# Teensylu2-1_0.net
KiCad netlist of a schematic drawn in EAGLE
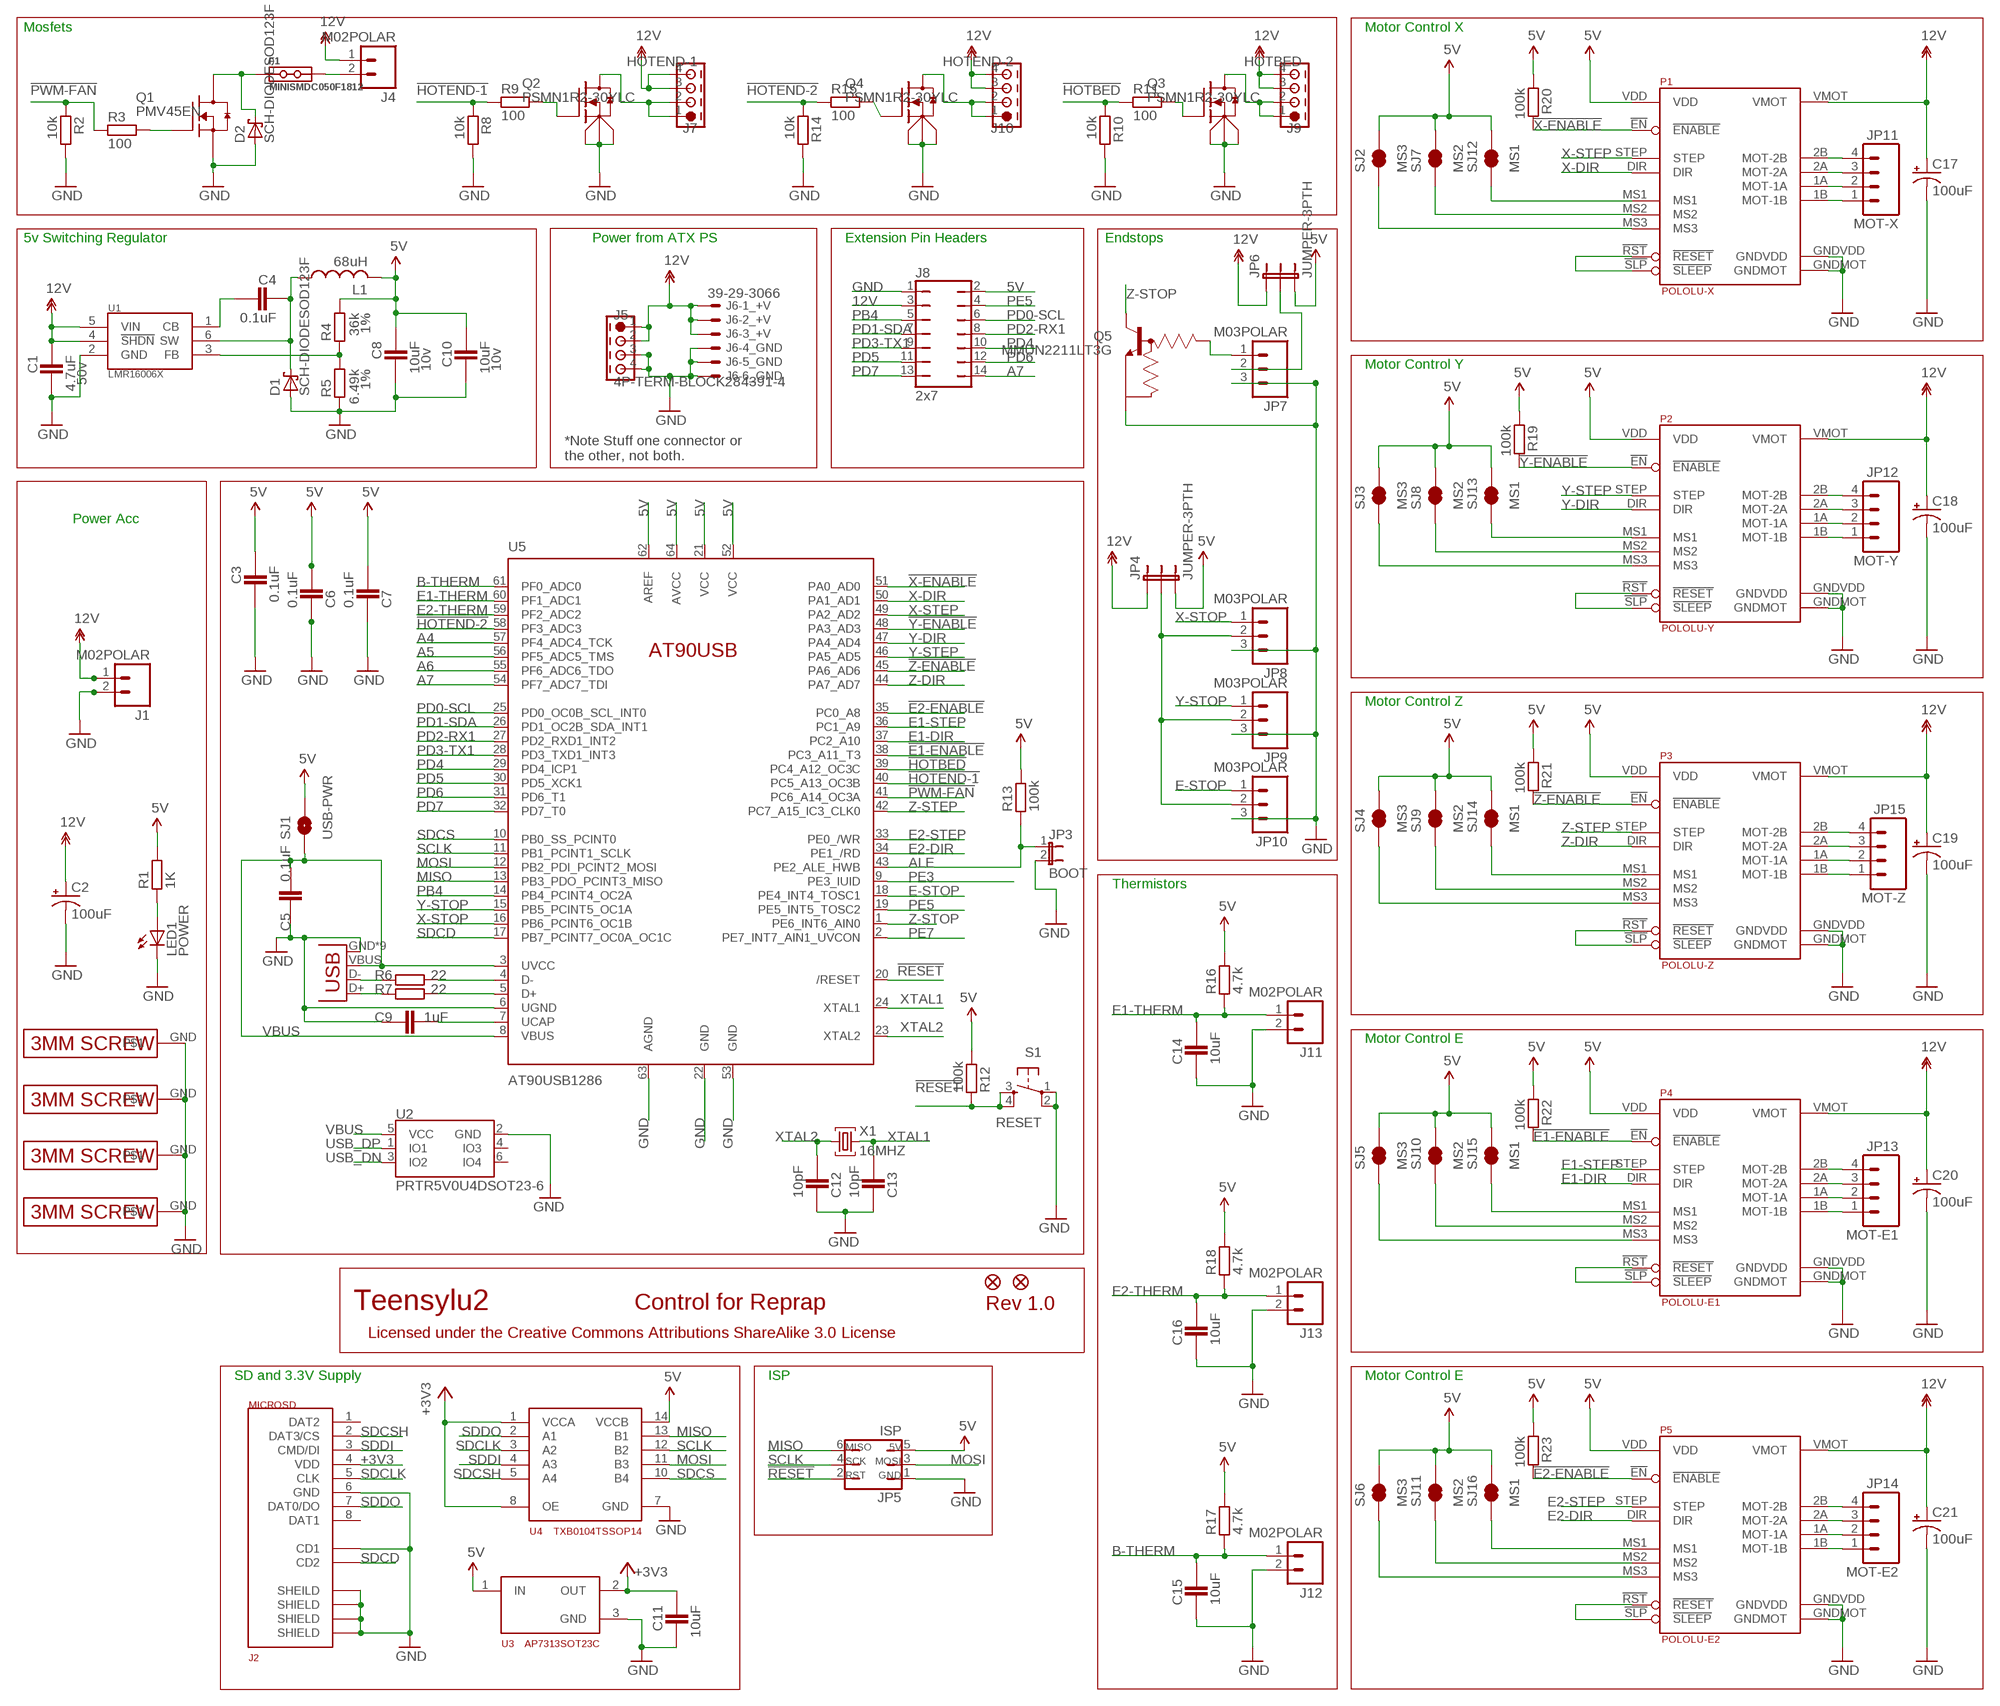
[diagram p0: schematic, sheet 1]

(export (version "E")
  (design (tool "Eeschema 10.0.6"))
  (components
    (comp (ref "C1")
      (value "4.7uF")
      (footprint "eagle-import:CAPC3215X168N")
      (fields
        (field (name "MANUFACTURER") "Yaiyo Yuden")
        (field (name "MANUFACTURER_PART_NUMBER") "UMK316AB7475KL-T")
        (field (name "TOLERANCE") "10%")
        (field (name "VDC") "50v")
      )
      (libsource (lib "eagle-import") (part "CAPACITOR_1206"))
    )
    (comp (ref "C2")
      (value "100uF")
      (footprint "eagle-import:PANASONIC_D")
      (fields
        (field (name "MANUFACTURER") "Panasonic")
        (field (name "MANUFACTURER_PART_NUMBER") "EEE-FTH101XAP")
        (field (name "TOLERANCE") "20%")
      )
      (libsource (lib "eagle-import") (part "CPOL-USD"))
    )
    (comp (ref "C3")
      (value "0.1uF")
      (footprint "eagle-import:CAPC1608X92N")
      (fields
        (field (name "MANUFACTURER") "Murata")
        (field (name "MANUFACTURER_PART_NUMBER") "GRM188R71C104KA01D")
        (field (name "TOLERANCE") "10%")
      )
      (libsource (lib "eagle-import") (part "CAPACITOR_0603"))
    )
    (comp (ref "C4")
      (value "0.1uF")
      (footprint "eagle-import:CAPC1608X92N")
      (fields
        (field (name "MANUFACTURER") "Samsung")
        (field (name "MANUFACTURER_PART_NUMBER") "CL10B104KB8NNNC")
        (field (name "TOLERANCE") "10%")
      )
      (libsource (lib "eagle-import") (part "CAPACITOR_0603"))
    )
    (comp (ref "C5")
      (value "0.1uF")
      (footprint "eagle-import:CAPC1608X92N")
      (fields
        (field (name "MANUFACTURER") "Murata")
        (field (name "MANUFACTURER_PART_NUMBER") "GRM188R71C104KA01D")
        (field (name "TOLERANCE") "10%")
      )
      (libsource (lib "eagle-import") (part "CAPACITOR_0603"))
    )
    (comp (ref "C6")
      (value "0.1uF")
      (footprint "eagle-import:CAPC1608X92N")
      (fields
        (field (name "MANUFACTURER") "Murata")
        (field (name "MANUFACTURER_PART_NUMBER") "GRM188R71C104KA01D")
        (field (name "TOLERANCE") "10%")
      )
      (libsource (lib "eagle-import") (part "CAPACITOR_0603"))
    )
    (comp (ref "C7")
      (value "0.1uF")
      (footprint "eagle-import:CAPC1608X92N")
      (fields
        (field (name "MANUFACTURER") "Murata")
        (field (name "MANUFACTURER_PART_NUMBER") "GRM188R71C104KA01D")
        (field (name "TOLERANCE") "10%")
      )
      (libsource (lib "eagle-import") (part "CAPACITOR_0603"))
    )
    (comp (ref "C8")
      (value "10uF")
      (footprint "eagle-import:CAPC2012X145AN")
      (fields
        (field (name "MANUFACTURER") "Murata")
        (field (name "MANUFACTURER_PART_NUMBER") "GRM21BR71A106KE51L")
        (field (name "TOLERANCE") "10%")
        (field (name "VDC") "10v")
      )
      (libsource (lib "eagle-import") (part "CAPACITOR_0805"))
    )
    (comp (ref "C9")
      (value "1uF")
      (footprint "eagle-import:CAPC1608X92N")
      (fields
        (field (name "MANUFACTURER") "Samsung")
        (field (name "MANUFACTURER_PART_NUMBER") "CL10A105MO8NNNC")
        (field (name "TOLERANCE") "20%")
      )
      (libsource (lib "eagle-import") (part "CAPACITOR_0603"))
    )
    (comp (ref "C10")
      (value "10uF")
      (footprint "eagle-import:CAPC2012X145AN")
      (fields
        (field (name "MANUFACTURER") "Murata")
        (field (name "MANUFACTURER_PART_NUMBER") "GRM21BR71A106KE51L")
        (field (name "TOLERANCE") "10%")
        (field (name "VDC") "10v")
      )
      (libsource (lib "eagle-import") (part "CAPACITOR_0805"))
    )
    (comp (ref "C11")
      (value "10uF")
      (footprint "eagle-import:CAPC1608X92N")
      (fields
        (field (name "MANUFACTURER") "Murata")
        (field (name "MANUFACTURER_PART_NUMBER") "GRM188R61C106MA73D")
        (field (name "TOLERANCE") "20%")
      )
      (libsource (lib "eagle-import") (part "CAPACITOR_0603"))
    )
    (comp (ref "C12")
      (value "10pF")
      (footprint "eagle-import:CAPC1608X92N")
      (fields
        (field (name "MANUFACTURER") "Samsung")
        (field (name "MANUFACTURER_PART_NUMBER") "CL10C100JB8NCNC")
        (field (name "TOLERANCE") "5%")
      )
      (libsource (lib "eagle-import") (part "CAPACITOR_0603"))
    )
    (comp (ref "C13")
      (value "10pF")
      (footprint "eagle-import:CAPC1608X92N")
      (fields
        (field (name "MANUFACTURER") "Samsung")
        (field (name "MANUFACTURER_PART_NUMBER") "CL10C100JB8NCNC")
        (field (name "TOLERANCE") "5%")
      )
      (libsource (lib "eagle-import") (part "CAPACITOR_0603"))
    )
    (comp (ref "C14")
      (value "10uF")
      (footprint "eagle-import:CAPC1608X92N")
      (fields
        (field (name "MANUFACTURER") "Murata")
        (field (name "MANUFACTURER_PART_NUMBER") "GRM188R61C106MA73D")
        (field (name "TOLERANCE") "20%")
      )
      (libsource (lib "eagle-import") (part "CAPACITOR_0603"))
    )
    (comp (ref "C15")
      (value "10uF")
      (footprint "eagle-import:CAPC1608X92N")
      (fields
        (field (name "MANUFACTURER") "Murata")
        (field (name "MANUFACTURER_PART_NUMBER") "GRM188R61C106MA73D")
        (field (name "TOLERANCE") "20%")
      )
      (libsource (lib "eagle-import") (part "CAPACITOR_0603"))
    )
    (comp (ref "C16")
      (value "10uF")
      (footprint "eagle-import:CAPC1608X92N")
      (fields
        (field (name "MANUFACTURER") "Murata")
        (field (name "MANUFACTURER_PART_NUMBER") "GRM188R61C106MA73D")
        (field (name "TOLERANCE") "20%")
      )
      (libsource (lib "eagle-import") (part "CAPACITOR_0603"))
    )
    (comp (ref "C17")
      (value "100uF")
      (footprint "eagle-import:PANASONIC_D")
      (fields
        (field (name "MANUFACTURER") "Panasonic")
        (field (name "MANUFACTURER_PART_NUMBER") "EEE-FTH101XAP")
        (field (name "TOLERANCE") "20%")
      )
      (libsource (lib "eagle-import") (part "CPOL-USD"))
    )
    (comp (ref "C18")
      (value "100uF")
      (footprint "eagle-import:PANASONIC_D")
      (fields
        (field (name "MANUFACTURER") "Panasonic")
        (field (name "MANUFACTURER_PART_NUMBER") "EEE-FTH101XAP")
        (field (name "TOLERANCE") "20%")
      )
      (libsource (lib "eagle-import") (part "CPOL-USD"))
    )
    (comp (ref "C19")
      (value "100uF")
      (footprint "eagle-import:PANASONIC_D")
      (fields
        (field (name "MANUFACTURER") "Panasonic")
        (field (name "MANUFACTURER_PART_NUMBER") "EEE-FTH101XAP")
        (field (name "TOLERANCE") "20%")
      )
      (libsource (lib "eagle-import") (part "CPOL-USD"))
    )
    (comp (ref "C20")
      (value "100uF")
      (footprint "eagle-import:PANASONIC_D")
      (fields
        (field (name "MANUFACTURER") "Panasonic")
        (field (name "MANUFACTURER_PART_NUMBER") "EEE-FTH101XAP")
        (field (name "TOLERANCE") "20%")
      )
      (libsource (lib "eagle-import") (part "CPOL-USD"))
    )
    (comp (ref "C21")
      (value "100uF")
      (footprint "eagle-import:PANASONIC_D")
      (fields
        (field (name "MANUFACTURER") "Panasonic")
        (field (name "MANUFACTURER_PART_NUMBER") "EEE-FTH101XAP")
        (field (name "TOLERANCE") "20%")
      )
      (libsource (lib "eagle-import") (part "CPOL-USD"))
    )
    (comp (ref "D1")
      (value "SCH-DIODESOD123F")
      (footprint "eagle-import:SOD123F")
      (fields
        (field (name "MANUFACTURER") "NXP Semiconductors")
        (field (name "MANUFACTURER_PART_NUMBER") "PMEG4010CEH,115")
        (field (name "CURRENT") "1A")
        (field (name "MANUFACTURER_1") "NXP Semiconductors")
        (field (name "MANUFACTURER_PART_NUMBER_1") "PMEG4010CEH,115")
        (field (name "REVERSE_VOLTAGE") "40V")
      )
      (libsource (lib "eagle-import") (part "SCH-DIODESOD123F"))
    )
    (comp (ref "D2")
      (value "SCH-DIODESOD123F")
      (footprint "eagle-import:SOD123F")
      (fields
        (field (name "MANUFACTURER") "NXP Semiconductors")
        (field (name "MANUFACTURER_PART_NUMBER") "PMEG4010CEH,115")
        (field (name "CURRENT") "1A")
        (field (name "MANUFACTURER_1") "NXP Semiconductors")
      )
      (libsource (lib "eagle-import") (part "SCH-DIODESOD123F"))
    )
    (comp (ref "F1")
      (value "MINISMDC050F1812")
      (footprint "eagle-import:MINISMDC")
      (fields
        (field (name "MANUFACTURER") "TE Connectivity")
        (field (name "MANUFACTURER_PART_NUMBER") "MINISMDC050F-2")
      )
      (libsource (lib "eagle-import") (part "MINISMDC050F1812"))
    )
    (comp (ref "J1")
      (value "M02POLAR")
      (footprint "eagle-import:MOLEX-1X2")
      (description "CONN HEADER 2POS .100 VERT TIN")
      (fields (field (name "MANUFACTURER") "Molex") (field (name "MANUFACTURER_PART_NUMBER") "0022272021"))
      (libsource (lib "eagle-import") (part "M02POLAR"))
    )
    (comp (ref "J2")
      (value "MICROSD")
      (footprint "eagle-import:AMPHENOL-MICROSD")
      (description "CONN MICRO SD CARD PUSH-PULL R/A")
      (fields
        (field (name "MANUFACTURER") "Amphenol")
        (field (name "MANUFACTURER_PART_NUMBER") "114-00841-68")
      )
      (libsource (lib "eagle-import") (part "MICROSD"))
    )
    (comp (ref "J3")
      (value "USB-MICRO-PTH")
      (footprint "eagle-import:USB-MICROB-PTH")
      (fields (field (name "MANUFACTURER") "FCI") (field (name "MANUFACTURER_PART_NUMBER") "10118194-0001LF"))
      (libsource (lib "eagle-import") (part "USB-MICRO-PTH"))
    )
    (comp (ref "J4")
      (value "M02POLAR")
      (footprint "eagle-import:MOLEX-1X2")
      (description "CONN HEADER 2POS .100 VERT TIN")
      (fields (field (name "MANUFACTURER") "Molex") (field (name "MANUFACTURER_PART_NUMBER") "0022272021"))
      (libsource (lib "eagle-import") (part "M02POLAR"))
    )
    (comp (ref "J5")
      (value "4P-TERM-BLOCK284391-4")
      (footprint "eagle-import:284391-4")
      (fields
        (field (name "MANUFACTURER") "TE Connectivity")
        (field (name "MANUFACTURER_PART_NUMBER") "284391-4")
      )
      (libsource (lib "eagle-import") (part "4P-TERM-BLOCK284391-4"))
    )
    (comp (ref "J6")
      (value "39-29-3066")
      (footprint "eagle-import:39-29-3066")
      (fields (field (name "MANUFACTURER") "Molex") (field (name "MANUFACTURER_PART_NUMBER") "0039293066"))
      (libsource (lib "eagle-import") (part "39-29-3066"))
    )
    (comp (ref "J7")
      (value "HOTEND-1")
      (footprint "eagle-import:282834-4")
      (fields
        (field (name "MANUFACTURER") "TE Connectivity")
        (field (name "MANUFACTURER_PART_NUMBER") "282834-4")
      )
      (libsource (lib "eagle-import") (part "4P-TERM-BLOCK282834-4"))
    )
    (comp (ref "J8")
      (value "2x7")
      (footprint "eagle-import:JP7Q")
      (description "DIL VERTICAL PC TAIL PIN HEADER")
      (fields (field (name "MANUFACTURER") "Harwin") (field (name "MANUFACTURER_PART_NUMBER") "M20-9980746"))
      (libsource (lib "eagle-import") (part "JP7Q"))
    )
    (comp (ref "J9")
      (value "HOTBED")
      (footprint "eagle-import:284391-4")
      (fields
        (field (name "MANUFACTURER") "TE Connectivity")
        (field (name "MANUFACTURER_PART_NUMBER") "284391-4")
      )
      (libsource (lib "eagle-import") (part "4P-TERM-BLOCK284391-4"))
    )
    (comp (ref "J10")
      (value "HOTEND-2")
      (footprint "eagle-import:282834-4")
      (fields
        (field (name "MANUFACTURER") "TE Connectivity")
        (field (name "MANUFACTURER_PART_NUMBER") "282834-4")
      )
      (libsource (lib "eagle-import") (part "4P-TERM-BLOCK282834-4"))
    )
    (comp (ref "J11")
      (value "M02POLAR")
      (footprint "eagle-import:MOLEX-1X2")
      (description "CONN HEADER 2POS .100 VERT TIN")
      (fields (field (name "MANUFACTURER") "Molex") (field (name "MANUFACTURER_PART_NUMBER") "0022272021"))
      (libsource (lib "eagle-import") (part "M02POLAR"))
    )
    (comp (ref "J12")
      (value "M02POLAR")
      (footprint "eagle-import:MOLEX-1X2")
      (description "CONN HEADER 2POS .100 VERT TIN")
      (fields (field (name "MANUFACTURER") "Molex") (field (name "MANUFACTURER_PART_NUMBER") "0022272021"))
      (libsource (lib "eagle-import") (part "M02POLAR"))
    )
    (comp (ref "J13")
      (value "M02POLAR")
      (footprint "eagle-import:MOLEX-1X2")
      (description "CONN HEADER 2POS .100 VERT TIN")
      (fields (field (name "MANUFACTURER") "Molex") (field (name "MANUFACTURER_PART_NUMBER") "0022272021"))
      (libsource (lib "eagle-import") (part "M02POLAR"))
    )
    (comp (ref "JP1")
      (value "FIDUCIAL1X2.5")
      (footprint "eagle-import:FIDUCIAL-1X2.5")
      (libsource (lib "eagle-import") (part "FIDUCIAL1X2.5"))
    )
    (comp (ref "JP2")
      (value "FIDUCIAL1X2.5")
      (footprint "eagle-import:FIDUCIAL-1X2.5")
      (libsource (lib "eagle-import") (part "FIDUCIAL1X2.5"))
    )
    (comp (ref "JP3")
      (value "BOOT")
      (footprint "eagle-import:1X02")
      (description "SIL VERTICAL PC TAIL PIN HEADER")
      (fields (field (name "MANUFACTURER") "Harwin") (field (name "MANUFACTURER_PART_NUMBER") "M20-9990246"))
      (libsource (lib "eagle-import") (part "JUMPER-2PTH"))
    )
    (comp (ref "JP4")
      (value "JUMPER-3PTH")
      (footprint "eagle-import:1X03")
      (libsource (lib "eagle-import") (part "JUMPER-3PTH"))
    )
    (comp (ref "JP5")
      (value "ISP")
      (footprint "eagle-import:ISP")
      (libsource (lib "eagle-import") (part "PROGHEADER"))
    )
    (comp (ref "JP6")
      (value "JUMPER-3PTH")
      (footprint "eagle-import:1X03")
      (libsource (lib "eagle-import") (part "JUMPER-3PTH"))
    )
    (comp (ref "JP7")
      (value "M03POLAR")
      (footprint "eagle-import:MOLEX-1X3")
      (description "CONN HEADER 3POS .100 VERT TIN")
      (fields (field (name "MANUFACTURER") "Molex") (field (name "MANUFACTURER_PART_NUMBER") "0022272031"))
      (libsource (lib "eagle-import") (part "M03POLAR"))
    )
    (comp (ref "JP8")
      (value "M03POLAR")
      (footprint "eagle-import:MOLEX-1X3")
      (description "CONN HEADER 3POS .100 VERT TIN")
      (fields (field (name "MANUFACTURER") "Molex") (field (name "MANUFACTURER_PART_NUMBER") "0022272031"))
      (libsource (lib "eagle-import") (part "M03POLAR"))
    )
    (comp (ref "JP9")
      (value "M03POLAR")
      (footprint "eagle-import:MOLEX-1X3")
      (description "CONN HEADER 3POS .100 VERT TIN")
      (fields (field (name "MANUFACTURER") "Molex") (field (name "MANUFACTURER_PART_NUMBER") "0022272031"))
      (libsource (lib "eagle-import") (part "M03POLAR"))
    )
    (comp (ref "JP10")
      (value "M03POLAR")
      (footprint "eagle-import:MOLEX-1X3")
      (description "CONN HEADER 3POS .100 VERT TIN")
      (fields (field (name "MANUFACTURER") "Molex") (field (name "MANUFACTURER_PART_NUMBER") "0022272031"))
      (libsource (lib "eagle-import") (part "M03POLAR"))
    )
    (comp (ref "JP11")
      (value "MOT-X")
      (footprint "eagle-import:MOLEX-1X4")
      (fields (field (name "MANUFACTURER") "Molex") (field (name "MANUFACTURER_PART_NUMBER") "0022272041"))
      (libsource (lib "eagle-import") (part "M04POLAR"))
    )
    (comp (ref "JP12")
      (value "MOT-Y")
      (footprint "eagle-import:MOLEX-1X4")
      (fields (field (name "MANUFACTURER") "Molex") (field (name "MANUFACTURER_PART_NUMBER") "0022272041"))
      (libsource (lib "eagle-import") (part "M04POLAR"))
    )
    (comp (ref "JP13")
      (value "MOT-E1")
      (footprint "eagle-import:MOLEX-1X4")
      (fields (field (name "MANUFACTURER") "Molex") (field (name "MANUFACTURER_PART_NUMBER") "0022272041"))
      (libsource (lib "eagle-import") (part "M04POLAR"))
    )
    (comp (ref "JP14")
      (value "MOT-E2")
      (footprint "eagle-import:MOLEX-1X4")
      (fields (field (name "MANUFACTURER") "Molex") (field (name "MANUFACTURER_PART_NUMBER") "0022272041"))
      (libsource (lib "eagle-import") (part "M04POLAR"))
    )
    (comp (ref "JP15")
      (value "MOT-Z")
      (footprint "eagle-import:MOLEX-1X4")
      (fields (field (name "MANUFACTURER") "Molex") (field (name "MANUFACTURER_PART_NUMBER") "0022272041"))
      (libsource (lib "eagle-import") (part "M04POLAR"))
    )
    (comp (ref "L1")
      (value "68uH")
      (footprint "eagle-import:SRN6045")
      (fields
        (field (name "MANUFACTURER") "Bourns")
        (field (name "MANUFACTURER_PART_NUMBER") "SRN6045-680M")
        (field (name "MANUFACTURER_1") "Bourns")
        (field (name "MANUFACTURER_PART_NUMBER_1") "SRN6045-680M")
      )
      (libsource (lib "eagle-import") (part "INDUCTORSRN6045"))
    )
    (comp (ref "LED1")
      (value "POWER")
      (footprint "eagle-import:CHIPLED_0805")
      (fields
        (field (name "MANUFACTURER") "Kingbright")
        (field (name "MANUFACTURER_PART_NUMBER") "APT2012SGC")
      )
      (libsource (lib "eagle-import") (part "LEDCHIPLED_0805"))
    )
    (comp (ref "P1")
      (value "POLOLU-X")
      (footprint "eagle-import:POLOLU-STEPPER-PTH")
      (libsource (lib "eagle-import") (part "POLOLU-ALLEGRO"))
    )
    (comp (ref "P2")
      (value "POLOLU-Y")
      (footprint "eagle-import:POLOLU-STEPPER-PTH")
      (libsource (lib "eagle-import") (part "POLOLU-ALLEGRO"))
    )
    (comp (ref "P3")
      (value "POLOLU-Z")
      (footprint "eagle-import:POLOLU-STEPPER-PTH")
      (libsource (lib "eagle-import") (part "POLOLU-ALLEGRO"))
    )
    (comp (ref "P4")
      (value "POLOLU-E1")
      (footprint "eagle-import:POLOLU-STEPPER-PTH")
      (libsource (lib "eagle-import") (part "POLOLU-ALLEGRO"))
    )
    (comp (ref "P5")
      (value "POLOLU-E2")
      (footprint "eagle-import:POLOLU-STEPPER-PTH")
      (libsource (lib "eagle-import") (part "POLOLU-ALLEGRO"))
    )
    (comp (ref "Q1")
      (value "PMV45EN")
      (footprint "eagle-import:SOT23C")
      (fields
        (field (name "MANUFACTURER") "International Rectifier")
        (field (name "MANUFACTURER_PART_NUMBER") "IRLML2060TRPBF")
        (field (name "VOLTAGE") "60V")
      )
      (libsource (lib "eagle-import") (part "MOSFET-NCH_SOT-23"))
    )
    (comp (ref "Q2")
      (value "PSMN1R2-30YLC")
      (footprint "eagle-import:LFPACK-POWERPAK-SO8")
      (fields
        (field (name "MANUFACTURER") "NXP Semiconductors")
        (field (name "MANUFACTURER_PART_NUMBER") "PSMN1R2-30YLC,115")
        (field (name "VOLTAGE") "30V")
      )
      (libsource (lib "eagle-import") (part "PSMN1R2-30YLCPOWERPACK-S08"))
    )
    (comp (ref "Q3")
      (value "PSMN1R2-30YLC")
      (footprint "eagle-import:LFPACK-POWERPAK-SO8")
      (fields
        (field (name "MANUFACTURER") "NXP Semiconductors")
        (field (name "MANUFACTURER_PART_NUMBER") "PSMN1R2-30YLC,115")
        (field (name "VOLTAGE") "30V")
      )
      (libsource (lib "eagle-import") (part "PSMN1R2-30YLCPOWERPACK-S08"))
    )
    (comp (ref "Q4")
      (value "PSMN1R2-30YLC")
      (footprint "eagle-import:LFPACK-POWERPAK-SO8")
      (fields
        (field (name "MANUFACTURER") "NXP Semiconductors")
        (field (name "MANUFACTURER_PART_NUMBER") "PSMN1R2-30YLC,115")
        (field (name "VOLTAGE") "30V")
      )
      (libsource (lib "eagle-import") (part "PSMN1R2-30YLCPOWERPACK-S08"))
    )
    (comp (ref "Q5")
      (value "MMUN2211LT3G")
      (footprint "eagle-import:SOT23C")
      (description "TRANS PREBIAS NPN 246MW SOT23-3")
      (fields (field (name "MANUFACTURER") "ON Semiconductor"))
      (libsource (lib "eagle-import") (part "TRANSISTOR_NPN_BIASSOT23C"))
    )
    (comp (ref "R1")
      (value "1K")
      (footprint "eagle-import:RESC1608X55N")
      (libsource (lib "eagle-import") (part "RESISTOR_0603"))
    )
    (comp (ref "R2")
      (value "10k")
      (footprint "eagle-import:RESC1608X55N")
      (libsource (lib "eagle-import") (part "RESISTOR_0603"))
    )
    (comp (ref "R3")
      (value "100")
      (footprint "eagle-import:RESC1608X55N")
      (libsource (lib "eagle-import") (part "RESISTOR_0603"))
    )
    (comp (ref "R4")
      (value "36k")
      (footprint "eagle-import:RESC1608X55N")
      (fields (field (name "TOLERANCE") "1%"))
      (libsource (lib "eagle-import") (part "RESISTOR_0603"))
    )
    (comp (ref "R5")
      (value "6.49k")
      (footprint "eagle-import:RESC1608X55N")
      (fields (field (name "TOLERANCE") "1%"))
      (libsource (lib "eagle-import") (part "RESISTOR_0603"))
    )
    (comp (ref "R6")
      (value "22")
      (footprint "eagle-import:RESC1608X55N")
      (libsource (lib "eagle-import") (part "RESISTOR_0603"))
    )
    (comp (ref "R7")
      (value "22")
      (footprint "eagle-import:RESC1608X55N")
      (libsource (lib "eagle-import") (part "RESISTOR_0603"))
    )
    (comp (ref "R8")
      (value "10k")
      (footprint "eagle-import:RESC1608X55N")
      (libsource (lib "eagle-import") (part "RESISTOR_0603"))
    )
    (comp (ref "R9")
      (value "100")
      (footprint "eagle-import:RESC1608X55N")
      (libsource (lib "eagle-import") (part "RESISTOR_0603"))
    )
    (comp (ref "R10")
      (value "10k")
      (footprint "eagle-import:RESC1608X55N")
      (libsource (lib "eagle-import") (part "RESISTOR_0603"))
    )
    (comp (ref "R11")
      (value "100")
      (footprint "eagle-import:RESC1608X55N")
      (libsource (lib "eagle-import") (part "RESISTOR_0603"))
    )
    (comp (ref "R12")
      (value "100k")
      (footprint "eagle-import:RESC1608X55N")
      (libsource (lib "eagle-import") (part "RESISTOR_0603"))
    )
    (comp (ref "R13")
      (value "100k")
      (footprint "eagle-import:RESC1608X55N")
      (libsource (lib "eagle-import") (part "RESISTOR_0603"))
    )
    (comp (ref "R14")
      (value "10k")
      (footprint "eagle-import:RESC1608X55N")
      (libsource (lib "eagle-import") (part "RESISTOR_0603"))
    )
    (comp (ref "R15")
      (value "100")
      (footprint "eagle-import:RESC1608X55N")
      (libsource (lib "eagle-import") (part "RESISTOR_0603"))
    )
    (comp (ref "R16")
      (value "4.7k")
      (footprint "eagle-import:RESC1608X55N")
      (libsource (lib "eagle-import") (part "RESISTOR_0603"))
    )
    (comp (ref "R17")
      (value "4.7k")
      (footprint "eagle-import:RESC1608X55N")
      (libsource (lib "eagle-import") (part "RESISTOR_0603"))
    )
    (comp (ref "R18")
      (value "4.7k")
      (footprint "eagle-import:RESC1608X55N")
      (libsource (lib "eagle-import") (part "RESISTOR_0603"))
    )
    (comp (ref "R19")
      (value "100k")
      (footprint "eagle-import:RESC1608X55N")
      (libsource (lib "eagle-import") (part "RESISTOR_0603"))
    )
    (comp (ref "R20")
      (value "100k")
      (footprint "eagle-import:RESC1608X55N")
      (libsource (lib "eagle-import") (part "RESISTOR_0603"))
    )
    (comp (ref "R21")
      (value "100k")
      (footprint "eagle-import:RESC1608X55N")
      (libsource (lib "eagle-import") (part "RESISTOR_0603"))
    )
    (comp (ref "R22")
      (value "100k")
      (footprint "eagle-import:RESC1608X55N")
      (libsource (lib "eagle-import") (part "RESISTOR_0603"))
    )
    (comp (ref "R23")
      (value "100k")
      (footprint "eagle-import:RESC1608X55N")
      (libsource (lib "eagle-import") (part "RESISTOR_0603"))
    )
    (comp (ref "S1")
      (value "RESET")
      (footprint "eagle-import:TACTILE_SWITCH_SMD")
      (fields (field (name "MANUFACTURER") "Bourns") (field (name "MANUFACTURER_PART_NUMBER") "7914J-1-000E"))
      (libsource (lib "eagle-import") (part "TAC_SWITCHSMD"))
    )
    (comp (ref "SCREW1")
      (value "3MM-SCREW")
      (footprint "eagle-import:PLATEDSCREW")
      (libsource (lib "eagle-import") (part "3MM-SCREW"))
    )
    (comp (ref "SCREW2")
      (value "3MM-SCREW")
      (footprint "eagle-import:PLATEDSCREW")
      (libsource (lib "eagle-import") (part "3MM-SCREW"))
    )
    (comp (ref "SCREW3")
      (value "3MM-SCREW")
      (footprint "eagle-import:PLATEDSCREW")
      (libsource (lib "eagle-import") (part "3MM-SCREW"))
    )
    (comp (ref "SCREW4")
      (value "3MM-SCREW")
      (footprint "eagle-import:PLATEDSCREW")
      (libsource (lib "eagle-import") (part "3MM-SCREW"))
    )
    (comp (ref "SJ1")
      (value "USB-PWR")
      (footprint "eagle-import:SJ_2S-NO")
      (libsource (lib "eagle-import") (part "SOLDERJUMPERNO"))
    )
    (comp (ref "SJ2")
      (value "MS3")
      (footprint "eagle-import:SJ_2S-TRACE")
      (libsource (lib "eagle-import") (part "SOLDERJUMPER-NCSJ-TRACE"))
    )
    (comp (ref "SJ3")
      (value "MS3")
      (footprint "eagle-import:SJ_2S-TRACE")
      (libsource (lib "eagle-import") (part "SOLDERJUMPER-NCSJ-TRACE"))
    )
    (comp (ref "SJ4")
      (value "MS3")
      (footprint "eagle-import:SJ_2S-TRACE")
      (libsource (lib "eagle-import") (part "SOLDERJUMPER-NCSJ-TRACE"))
    )
    (comp (ref "SJ5")
      (value "MS3")
      (footprint "eagle-import:SJ_2S-TRACE")
      (libsource (lib "eagle-import") (part "SOLDERJUMPER-NCSJ-TRACE"))
    )
    (comp (ref "SJ6")
      (value "MS3")
      (footprint "eagle-import:SJ_2S-TRACE")
      (libsource (lib "eagle-import") (part "SOLDERJUMPER-NCSJ-TRACE"))
    )
    (comp (ref "SJ7")
      (value "MS2")
      (footprint "eagle-import:SJ_2S-TRACE")
      (libsource (lib "eagle-import") (part "SOLDERJUMPER-NCSJ-TRACE"))
    )
    (comp (ref "SJ8")
      (value "MS2")
      (footprint "eagle-import:SJ_2S-TRACE")
      (libsource (lib "eagle-import") (part "SOLDERJUMPER-NCSJ-TRACE"))
    )
    (comp (ref "SJ9")
      (value "MS2")
      (footprint "eagle-import:SJ_2S-TRACE")
      (libsource (lib "eagle-import") (part "SOLDERJUMPER-NCSJ-TRACE"))
    )
    (comp (ref "SJ10")
      (value "MS2")
      (footprint "eagle-import:SJ_2S-TRACE")
      (libsource (lib "eagle-import") (part "SOLDERJUMPER-NCSJ-TRACE"))
    )
    (comp (ref "SJ11")
      (value "MS2")
      (footprint "eagle-import:SJ_2S-TRACE")
      (libsource (lib "eagle-import") (part "SOLDERJUMPER-NCSJ-TRACE"))
    )
    (comp (ref "SJ12")
      (value "MS1")
      (footprint "eagle-import:SJ_2S-TRACE")
      (libsource (lib "eagle-import") (part "SOLDERJUMPER-NCSJ-TRACE"))
    )
    (comp (ref "SJ13")
      (value "MS1")
      (footprint "eagle-import:SJ_2S-TRACE")
      (libsource (lib "eagle-import") (part "SOLDERJUMPER-NCSJ-TRACE"))
    )
    (comp (ref "SJ14")
      (value "MS1")
      (footprint "eagle-import:SJ_2S-TRACE")
      (libsource (lib "eagle-import") (part "SOLDERJUMPER-NCSJ-TRACE"))
    )
    (comp (ref "SJ15")
      (value "MS1")
      (footprint "eagle-import:SJ_2S-TRACE")
      (libsource (lib "eagle-import") (part "SOLDERJUMPER-NCSJ-TRACE"))
    )
    (comp (ref "SJ16")
      (value "MS1")
      (footprint "eagle-import:SJ_2S-TRACE")
      (libsource (lib "eagle-import") (part "SOLDERJUMPER-NCSJ-TRACE"))
    )
    (comp (ref "U1")
      (value "LMR16006X")
      (footprint "eagle-import:TSOT6")
      (fields
        (field (name "MANUFACTURER") "Texas Instruments")
        (field (name "MANUFACTURER_PART_NUMBER") "LMR16006XDDCT")
      )
      (libsource (lib "eagle-import") (part "LMR16006X"))
    )
    (comp (ref "U2")
      (value "PRTR5V0U4DSOT23-6")
      (footprint "eagle-import:SOT23-6")
      (fields
        (field (name "MANUFACTURER") "NXP Semiconductors")
        (field (name "MANUFACTURER_PART_NUMBER") "PRTR5V0U4D,125")
      )
      (libsource (lib "eagle-import") (part "PRTR5V0U4DSOT23-6"))
    )
    (comp (ref "U3")
      (value "AP7313SOT23C")
      (footprint "eagle-import:SOT23C")
      (description "IC REG LDO 3.3V 0.15A SOT23-3")
      (fields
        (field (name "MANUFACTURER") "Diodes Incorporated")
        (field (name "MANUFACTURER_PART_NUMBER") "AP7313-33SAG-7")
      )
      (libsource (lib "eagle-import") (part "AP7313SOT23C"))
    )
    (comp (ref "U4")
      (value "TXB0104TSSOP14")
      (footprint "eagle-import:TSSOP14")
      (description "IC VOLT-LEVEL TRANSLATOR 14TSSOP")
      (fields
        (field (name "MANUFACTURER") "Texas Instruments")
        (field (name "MANUFACTURER_PART_NUMBER") "TXB0104PWR")
      )
      (libsource (lib "eagle-import") (part "TXB0104TSSOP14"))
    )
    (comp (ref "U5")
      (value "AT90USB1286")
      (footprint "eagle-import:TQFP64-2")
      (fields (field (name "MANUFACTURER") "Atmel"))
      (libsource (lib "eagle-import") (part "AT90USB"))
    )
    (comp (ref "X1")
      (value "16MHZ")
      (footprint "eagle-import:NDK-XTAL")
      (fields
        (field (name "MANUFACTURER") "NDK")
        (field (name "MANUFACTURER_PART_NUMBER") "NX5032GA-16.000000MHZ-LN-CD-1")
      )
      (libsource (lib "eagle-import") (part "XTAL"))
    )
  )
  (nets
    (net (code "1") (name "+3V3") (class "Default")
      (node (ref "C11") (pin "1") (pinfunction "1_1") (pintype "passive"))
      (node (ref "J2") (pin "4") (pinfunction "VDD_4") (pintype "power_in"))
      (node (ref "U3") (pin "2") (pinfunction "OUT_2") (pintype "power_in"))
      (node (ref "U4") (pin "1") (pinfunction "VCCA_1") (pintype "power_in"))
      (node (ref "U4") (pin "8") (pinfunction "OE_8") (pintype "input"))
    )
    (net (code "2") (name "/A4") (class "Default")
      (node (ref "U5") (pin "57") (pinfunction "PF4_ADC4_TCK_57") (pintype "bidirectional"))
    )
    (net (code "3") (name "/A5") (class "Default")
      (node (ref "U5") (pin "56") (pinfunction "PF5_ADC5_TMS_56") (pintype "bidirectional"))
    )
    (net (code "4") (name "/A6") (class "Default")
      (node (ref "U5") (pin "55") (pinfunction "PF6_ADC6_TDO_55") (pintype "bidirectional"))
    )
    (net (code "5") (name "/A7") (class "Default")
      (node (ref "J8") (pin "14") (pinfunction "14_14") (pintype "passive"))
      (node (ref "U5") (pin "54") (pinfunction "PF7_ADC7_TDI_54") (pintype "bidirectional"))
    )
    (net (code "6") (name "/ALE") (class "Default")
      (node (ref "JP3") (pin "1") (pinfunction "1_1") (pintype "passive"))
      (node (ref "R13") (pin "1") (pinfunction "1_1") (pintype "passive"))
      (node (ref "U5") (pin "43") (pinfunction "PE2_ALE_HWB_43") (pintype "bidirectional"))
    )
    (net (code "7") (name "/B-THERM") (class "Default")
      (node (ref "C15") (pin "2") (pinfunction "2_2") (pintype "passive"))
      (node (ref "J12") (pin "1") (pinfunction "1_1") (pintype "passive"))
      (node (ref "R17") (pin "1") (pinfunction "1_1") (pintype "passive"))
      (node (ref "U5") (pin "61") (pinfunction "PF0_ADC0_61") (pintype "bidirectional"))
    )
    (net (code "8") (name "/E-STOP") (class "Default")
      (node (ref "JP10") (pin "1") (pinfunction "1_1") (pintype "passive"))
      (node (ref "U5") (pin "18") (pinfunction "PE4_INT4_TOSC1_18") (pintype "bidirectional"))
    )
    (net (code "9") (name "/E1-DIR") (class "Default")
      (node (ref "P4") (pin "DIR") (pinfunction "DIR_DIR") (pintype "bidirectional"))
      (node (ref "U5") (pin "37") (pinfunction "PC2_A10_37") (pintype "bidirectional"))
    )
    (net (code "10") (name "/E1-STEP") (class "Default")
      (node (ref "P4") (pin "STEP") (pinfunction "STEP_STEP") (pintype "bidirectional"))
      (node (ref "U5") (pin "36") (pinfunction "PC1_A9_36") (pintype "bidirectional"))
    )
    (net (code "11") (name "/E1-THERM") (class "Default")
      (node (ref "C14") (pin "2") (pinfunction "2_2") (pintype "passive"))
      (node (ref "J11") (pin "1") (pinfunction "1_1") (pintype "passive"))
      (node (ref "R16") (pin "1") (pinfunction "1_1") (pintype "passive"))
      (node (ref "U5") (pin "60") (pinfunction "PF1_ADC1_60") (pintype "bidirectional"))
    )
    (net (code "12") (name "/E2-DIR") (class "Default")
      (node (ref "P5") (pin "DIR") (pinfunction "DIR_DIR") (pintype "bidirectional"))
      (node (ref "U5") (pin "34") (pinfunction "PE1_/RD_34") (pintype "bidirectional"))
    )
    (net (code "13") (name "/E2-STEP") (class "Default")
      (node (ref "P5") (pin "STEP") (pinfunction "STEP_STEP") (pintype "bidirectional"))
      (node (ref "U5") (pin "33") (pinfunction "PE0_/WR_33") (pintype "bidirectional"))
    )
    (net (code "14") (name "/E2-THERM") (class "Default")
      (node (ref "C16") (pin "2") (pinfunction "2_2") (pintype "passive"))
      (node (ref "J13") (pin "1") (pinfunction "1_1") (pintype "passive"))
      (node (ref "R18") (pin "1") (pinfunction "1_1") (pintype "passive"))
      (node (ref "U5") (pin "59") (pinfunction "PF2_ADC2_59") (pintype "bidirectional"))
    )
    (net (code "15") (name "/MISO") (class "Default")
      (node (ref "JP5") (pin "6") (pinfunction "6_6") (pintype "passive"))
      (node (ref "U4") (pin "13") (pinfunction "B1_13") (pintype "bidirectional"))
      (node (ref "U5") (pin "13") (pinfunction "PB3_PDO_PCINT3_MISO_13") (pintype "bidirectional"))
    )
    (net (code "16") (name "/MOSI") (class "Default")
      (node (ref "JP5") (pin "3") (pinfunction "3_3") (pintype "passive"))
      (node (ref "U4") (pin "11") (pinfunction "B3_11") (pintype "bidirectional"))
      (node (ref "U5") (pin "12") (pinfunction "PB2_PDI_PCINT2_MOSI_12") (pintype "bidirectional"))
    )
    (net (code "17") (name "/PB4") (class "Default")
      (node (ref "J8") (pin "5") (pinfunction "5_5") (pintype "passive"))
      (node (ref "U5") (pin "14") (pinfunction "PB4_PCINT4_OC2A_14") (pintype "bidirectional"))
    )
    (net (code "18") (name "/PD0-SCL") (class "Default")
      (node (ref "J8") (pin "6") (pinfunction "6_6") (pintype "passive"))
      (node (ref "U5") (pin "25") (pinfunction "PD0_OC0B_SCL_INT0_25") (pintype "bidirectional"))
    )
    (net (code "19") (name "/PD1-SDA") (class "Default")
      (node (ref "J8") (pin "7") (pinfunction "7_7") (pintype "passive"))
      (node (ref "U5") (pin "26") (pinfunction "PD1_OC2B_SDA_INT1_26") (pintype "bidirectional"))
    )
    (net (code "20") (name "/PD2-RX1") (class "Default")
      (node (ref "J8") (pin "8") (pinfunction "8_8") (pintype "passive"))
      (node (ref "U5") (pin "27") (pinfunction "PD2_RXD1_INT2_27") (pintype "bidirectional"))
    )
    (net (code "21") (name "/PD3-TX1") (class "Default")
      (node (ref "J8") (pin "9") (pinfunction "9_9") (pintype "passive"))
      (node (ref "U5") (pin "28") (pinfunction "PD3_TXD1_INT3_28") (pintype "bidirectional"))
    )
    (net (code "22") (name "/PD4") (class "Default")
      (node (ref "J8") (pin "10") (pinfunction "10_10") (pintype "passive"))
      (node (ref "U5") (pin "29") (pinfunction "PD4_ICP1_29") (pintype "bidirectional"))
    )
    (net (code "23") (name "/PD5") (class "Default")
      (node (ref "J8") (pin "11") (pinfunction "11_11") (pintype "passive"))
      (node (ref "U5") (pin "30") (pinfunction "PD5_XCK1_30") (pintype "bidirectional"))
    )
    (net (code "24") (name "/PD6") (class "Default")
      (node (ref "J8") (pin "12") (pinfunction "12_12") (pintype "passive"))
      (node (ref "U5") (pin "31") (pinfunction "PD6_T1_31") (pintype "bidirectional"))
    )
    (net (code "25") (name "/PD7") (class "Default")
      (node (ref "J8") (pin "13") (pinfunction "13_13") (pintype "passive"))
      (node (ref "U5") (pin "32") (pinfunction "PD7_T0_32") (pintype "bidirectional"))
    )
    (net (code "26") (name "/PE3") (class "Default")
      (node (ref "U5") (pin "9") (pinfunction "PE3_IUID_9") (pintype "bidirectional"))
    )
    (net (code "27") (name "/PE5") (class "Default")
      (node (ref "J8") (pin "4") (pinfunction "4_4") (pintype "passive"))
      (node (ref "U5") (pin "19") (pinfunction "PE5_INT5_TOSC2_19") (pintype "bidirectional"))
    )
    (net (code "28") (name "/PE7") (class "Default")
      (node (ref "U5") (pin "2") (pinfunction "PE7_INT7_AIN1_UVCON_2") (pintype "bidirectional"))
    )
    (net (code "29") (name "/SCLK") (class "Default")
      (node (ref "JP5") (pin "4") (pinfunction "4_4") (pintype "passive"))
      (node (ref "U4") (pin "12") (pinfunction "B2_12") (pintype "bidirectional"))
      (node (ref "U5") (pin "11") (pinfunction "PB1_PCINT1_SCLK_11") (pintype "bidirectional"))
    )
    (net (code "30") (name "/SDCD") (class "Default")
      (node (ref "J2") (pin "CD2") (pinfunction "CD2_CD2") (pintype "bidirectional"))
      (node (ref "U5") (pin "17") (pinfunction "PB7_PCINT7_OC0A_OC1C_17") (pintype "bidirectional"))
    )
    (net (code "31") (name "/SDCLK") (class "Default")
      (node (ref "J2") (pin "5") (pinfunction "CLK_5") (pintype "input"))
      (node (ref "U4") (pin "3") (pinfunction "A2_3") (pintype "bidirectional"))
    )
    (net (code "32") (name "/SDCS") (class "Default")
      (node (ref "U4") (pin "10") (pinfunction "B4_10") (pintype "bidirectional"))
      (node (ref "U5") (pin "10") (pinfunction "PB0_SS_PCINT0_10") (pintype "bidirectional"))
    )
    (net (code "33") (name "/SDCSH") (class "Default")
      (node (ref "J2") (pin "2") (pinfunction "DAT3/CS_2") (pintype "bidirectional"))
      (node (ref "U4") (pin "5") (pinfunction "A4_5") (pintype "bidirectional"))
    )
    (net (code "34") (name "/SDDI") (class "Default")
      (node (ref "J2") (pin "3") (pinfunction "CMD/DI_3") (pintype "input"))
      (node (ref "U4") (pin "4") (pinfunction "A3_4") (pintype "bidirectional"))
    )
    (net (code "35") (name "/SDDO") (class "Default")
      (node (ref "J2") (pin "7") (pinfunction "DAT0/DO_7") (pintype "bidirectional"))
      (node (ref "U4") (pin "2") (pinfunction "A1_2") (pintype "bidirectional"))
    )
    (net (code "36") (name "/USB_DN") (class "Default")
      (node (ref "J3") (pin "D-") (pinfunction "D-_D-") (pintype "bidirectional"))
      (node (ref "R6") (pin "1") (pinfunction "1_1") (pintype "passive"))
      (node (ref "U2") (pin "3") (pinfunction "IO2_3") (pintype "bidirectional"))
    )
    (net (code "37") (name "/USB_DP") (class "Default")
      (node (ref "J3") (pin "D+") (pinfunction "D+_D+") (pintype "bidirectional"))
      (node (ref "R7") (pin "1") (pinfunction "1_1") (pintype "passive"))
      (node (ref "U2") (pin "1") (pinfunction "IO1_1") (pintype "bidirectional"))
    )
    (net (code "38") (name "/VBUS") (class "Default")
      (node (ref "C5") (pin "2") (pinfunction "2_2") (pintype "passive"))
      (node (ref "J3") (pin "VBUS") (pinfunction "VBUS_VBUS") (pintype "bidirectional"))
      (node (ref "SJ1") (pin "1") (pinfunction "1_1") (pintype "passive"))
      (node (ref "U2") (pin "5") (pinfunction "VCC_5") (pintype "power_in"))
      (node (ref "U5") (pin "3") (pinfunction "UVCC_3") (pintype "power_in"))
      (node (ref "U5") (pin "8") (pinfunction "VBUS_8") (pintype "bidirectional"))
    )
    (net (code "39") (name "/X-DIR") (class "Default")
      (node (ref "P1") (pin "DIR") (pinfunction "DIR_DIR") (pintype "bidirectional"))
      (node (ref "U5") (pin "50") (pinfunction "PA1_AD1_50") (pintype "bidirectional"))
    )
    (net (code "40") (name "/X-STEP") (class "Default")
      (node (ref "P1") (pin "STEP") (pinfunction "STEP_STEP") (pintype "bidirectional"))
      (node (ref "U5") (pin "49") (pinfunction "PA2_AD2_49") (pintype "bidirectional"))
    )
    (net (code "41") (name "/X-STOP") (class "Default")
      (node (ref "JP8") (pin "1") (pinfunction "1_1") (pintype "passive"))
      (node (ref "U5") (pin "16") (pinfunction "PB6_PCINT6_OC1B_16") (pintype "bidirectional"))
    )
    (net (code "42") (name "/XTAL1") (class "Default")
      (node (ref "C13") (pin "2") (pinfunction "2_2") (pintype "passive"))
      (node (ref "U5") (pin "24") (pinfunction "XTAL1_24") (pintype "passive"))
      (node (ref "X1") (pin "P$2") (pinfunction "2_P$2") (pintype "passive"))
    )
    (net (code "43") (name "/XTAL2") (class "Default")
      (node (ref "C12") (pin "2") (pinfunction "2_2") (pintype "passive"))
      (node (ref "U5") (pin "23") (pinfunction "XTAL2_23") (pintype "passive"))
      (node (ref "X1") (pin "P$1") (pinfunction "1_P$1") (pintype "passive"))
    )
    (net (code "44") (name "/Y-DIR") (class "Default")
      (node (ref "P2") (pin "DIR") (pinfunction "DIR_DIR") (pintype "bidirectional"))
      (node (ref "U5") (pin "47") (pinfunction "PA4_AD4_47") (pintype "bidirectional"))
    )
    (net (code "45") (name "/Y-STEP") (class "Default")
      (node (ref "P2") (pin "STEP") (pinfunction "STEP_STEP") (pintype "bidirectional"))
      (node (ref "U5") (pin "46") (pinfunction "PA5_AD5_46") (pintype "bidirectional"))
    )
    (net (code "46") (name "/Y-STOP") (class "Default")
      (node (ref "JP9") (pin "1") (pinfunction "1_1") (pintype "passive"))
      (node (ref "U5") (pin "15") (pinfunction "PB5_PCINT5_OC1A_15") (pintype "bidirectional"))
    )
    (net (code "47") (name "/Z-DIR") (class "Default")
      (node (ref "P3") (pin "DIR") (pinfunction "DIR_DIR") (pintype "bidirectional"))
      (node (ref "U5") (pin "44") (pinfunction "PA7_AD7_44") (pintype "bidirectional"))
    )
    (net (code "48") (name "/Z-STEP") (class "Default")
      (node (ref "P3") (pin "STEP") (pinfunction "STEP_STEP") (pintype "bidirectional"))
      (node (ref "U5") (pin "42") (pinfunction "PC7_A15_IC3_CLK0_42") (pintype "bidirectional"))
    )
    (net (code "49") (name "/Z-STOP") (class "Default")
      (node (ref "Q5") (pin "3") (pinfunction "C_3") (pintype "passive"))
      (node (ref "U5") (pin "1") (pinfunction "PE6_INT6_AIN0_1") (pintype "bidirectional"))
    )
    (net (code "50") (name "/~{E1-ENABLE}") (class "Default")
      (node (ref "P4") (pin "!EN") (pinfunction "~{ENABLE}_!EN") (pintype "input"))
      (node (ref "R22") (pin "2") (pinfunction "2_2") (pintype "passive"))
      (node (ref "U5") (pin "38") (pinfunction "PC3_A11_T3_38") (pintype "bidirectional"))
    )
    (net (code "51") (name "/~{E2-ENABLE}") (class "Default")
      (node (ref "P5") (pin "!EN") (pinfunction "~{ENABLE}_!EN") (pintype "input"))
      (node (ref "R23") (pin "2") (pinfunction "2_2") (pintype "passive"))
      (node (ref "U5") (pin "35") (pinfunction "PC0_A8_35") (pintype "bidirectional"))
    )
    (net (code "52") (name "/~{HOTBED}") (class "Default")
      (node (ref "R10") (pin "1") (pinfunction "1_1") (pintype "passive"))
      (node (ref "R11") (pin "1") (pinfunction "1_1") (pintype "passive"))
      (node (ref "U5") (pin "39") (pinfunction "PC4_A12_OC3C_39") (pintype "bidirectional"))
    )
    (net (code "53") (name "/~{HOTEND-1}") (class "Default")
      (node (ref "R8") (pin "1") (pinfunction "1_1") (pintype "passive"))
      (node (ref "R9") (pin "1") (pinfunction "1_1") (pintype "passive"))
      (node (ref "U5") (pin "40") (pinfunction "PC5_A13_OC3B_40") (pintype "bidirectional"))
    )
    (net (code "54") (name "/~{HOTEND-2}") (class "Default")
      (node (ref "R14") (pin "1") (pinfunction "1_1") (pintype "passive"))
      (node (ref "R15") (pin "1") (pinfunction "1_1") (pintype "passive"))
      (node (ref "U5") (pin "58") (pinfunction "PF3_ADC3_58") (pintype "bidirectional"))
    )
    (net (code "55") (name "/~{PWM-FAN}") (class "Default")
      (node (ref "R2") (pin "1") (pinfunction "1_1") (pintype "passive"))
      (node (ref "R3") (pin "1") (pinfunction "1_1") (pintype "passive"))
      (node (ref "U5") (pin "41") (pinfunction "PC6_A14_OC3A_41") (pintype "bidirectional"))
    )
    (net (code "56") (name "/~{RESET}") (class "Default")
      (node (ref "JP5") (pin "2") (pinfunction "2_2") (pintype "passive"))
      (node (ref "R12") (pin "1") (pinfunction "1_1") (pintype "passive"))
      (node (ref "S1") (pin "3") (pinfunction "3_3") (pintype "passive"))
      (node (ref "S1") (pin "4") (pinfunction "4_4") (pintype "passive"))
      (node (ref "U5") (pin "20") (pinfunction "/RESET_20") (pintype "bidirectional"))
    )
    (net (code "57") (name "/~{X-ENABLE}") (class "Default")
      (node (ref "P1") (pin "!EN") (pinfunction "~{ENABLE}_!EN") (pintype "input"))
      (node (ref "R20") (pin "2") (pinfunction "2_2") (pintype "passive"))
      (node (ref "U5") (pin "51") (pinfunction "PA0_AD0_51") (pintype "bidirectional"))
    )
    (net (code "58") (name "/~{Y-ENABLE}") (class "Default")
      (node (ref "P2") (pin "!EN") (pinfunction "~{ENABLE}_!EN") (pintype "input"))
      (node (ref "R19") (pin "2") (pinfunction "2_2") (pintype "passive"))
      (node (ref "U5") (pin "48") (pinfunction "PA3_AD3_48") (pintype "bidirectional"))
    )
    (net (code "59") (name "/~{Z-ENABLE}") (class "Default")
      (node (ref "P3") (pin "!EN") (pinfunction "~{ENABLE}_!EN") (pintype "input"))
      (node (ref "R21") (pin "2") (pinfunction "2_2") (pintype "passive"))
      (node (ref "U5") (pin "45") (pinfunction "PA6_AD6_45") (pintype "bidirectional"))
    )
    (net (code "60") (name "5V") (class "Default")
      (node (ref "C10") (pin "1") (pinfunction "1_1") (pintype "passive"))
      (node (ref "C3") (pin "1") (pinfunction "1_1") (pintype "passive"))
      (node (ref "C6") (pin "2") (pinfunction "2_2") (pintype "passive"))
      (node (ref "C7") (pin "2") (pinfunction "2_2") (pintype "passive"))
      (node (ref "C8") (pin "1") (pinfunction "1_1") (pintype "passive"))
      (node (ref "J8") (pin "2") (pinfunction "2_2") (pintype "passive"))
      (node (ref "JP4") (pin "3") (pinfunction "3_3") (pintype "passive"))
      (node (ref "JP5") (pin "5") (pinfunction "5_5") (pintype "passive"))
      (node (ref "JP6") (pin "3") (pinfunction "3_3") (pintype "passive"))
      (node (ref "L1") (pin "2") (pinfunction "2_2") (pintype "passive"))
      (node (ref "P1") (pin "VDD") (pinfunction "VDD_VDD") (pintype "power_in"))
      (node (ref "P2") (pin "VDD") (pinfunction "VDD_VDD") (pintype "power_in"))
      (node (ref "P3") (pin "VDD") (pinfunction "VDD_VDD") (pintype "power_in"))
      (node (ref "P4") (pin "VDD") (pinfunction "VDD_VDD") (pintype "power_in"))
      (node (ref "P5") (pin "VDD") (pinfunction "VDD_VDD") (pintype "power_in"))
      (node (ref "R1") (pin "2") (pinfunction "2_2") (pintype "passive"))
      (node (ref "R12") (pin "2") (pinfunction "2_2") (pintype "passive"))
      (node (ref "R13") (pin "2") (pinfunction "2_2") (pintype "passive"))
      (node (ref "R16") (pin "2") (pinfunction "2_2") (pintype "passive"))
      (node (ref "R17") (pin "2") (pinfunction "2_2") (pintype "passive"))
      (node (ref "R18") (pin "2") (pinfunction "2_2") (pintype "passive"))
      (node (ref "R19") (pin "1") (pinfunction "1_1") (pintype "passive"))
      (node (ref "R20") (pin "1") (pinfunction "1_1") (pintype "passive"))
      (node (ref "R21") (pin "1") (pinfunction "1_1") (pintype "passive"))
      (node (ref "R22") (pin "1") (pinfunction "1_1") (pintype "passive"))
      (node (ref "R23") (pin "1") (pinfunction "1_1") (pintype "passive"))
      (node (ref "R4") (pin "1") (pinfunction "1_1") (pintype "passive"))
      (node (ref "SJ1") (pin "2") (pinfunction "2_2") (pintype "passive"))
      (node (ref "SJ10") (pin "2") (pinfunction "2_2") (pintype "passive"))
      (node (ref "SJ11") (pin "2") (pinfunction "2_2") (pintype "passive"))
      (node (ref "SJ12") (pin "2") (pinfunction "2_2") (pintype "passive"))
      (node (ref "SJ13") (pin "2") (pinfunction "2_2") (pintype "passive"))
      (node (ref "SJ14") (pin "2") (pinfunction "2_2") (pintype "passive"))
      (node (ref "SJ15") (pin "2") (pinfunction "2_2") (pintype "passive"))
      (node (ref "SJ16") (pin "2") (pinfunction "2_2") (pintype "passive"))
      (node (ref "SJ2") (pin "2") (pinfunction "2_2") (pintype "passive"))
      (node (ref "SJ3") (pin "2") (pinfunction "2_2") (pintype "passive"))
      (node (ref "SJ4") (pin "2") (pinfunction "2_2") (pintype "passive"))
      (node (ref "SJ5") (pin "2") (pinfunction "2_2") (pintype "passive"))
      (node (ref "SJ6") (pin "2") (pinfunction "2_2") (pintype "passive"))
      (node (ref "SJ7") (pin "2") (pinfunction "2_2") (pintype "passive"))
      (node (ref "SJ8") (pin "2") (pinfunction "2_2") (pintype "passive"))
      (node (ref "SJ9") (pin "2") (pinfunction "2_2") (pintype "passive"))
      (node (ref "U3") (pin "1") (pinfunction "IN_1") (pintype "power_in"))
      (node (ref "U4") (pin "14") (pinfunction "VCCB_14") (pintype "power_in"))
      (node (ref "U5") (pin "21") (pinfunction "VCC_21") (pintype "power_in"))
      (node (ref "U5") (pin "52") (pinfunction "VCC_52") (pintype "power_in"))
      (node (ref "U5") (pin "62") (pinfunction "AREF_62") (pintype "power_in"))
      (node (ref "U5") (pin "64") (pinfunction "AVCC_64") (pintype "power_in"))
    )
    (net (code "61") (name "12V") (class "Default")
      (node (ref "C1") (pin "1") (pinfunction "1_1") (pintype "passive"))
      (node (ref "C17") (pin "+") (pinfunction "+_+") (pintype "passive"))
      (node (ref "C18") (pin "+") (pinfunction "+_+") (pintype "passive"))
      (node (ref "C19") (pin "+") (pinfunction "+_+") (pintype "passive"))
      (node (ref "C2") (pin "+") (pinfunction "+_+") (pintype "passive"))
      (node (ref "C20") (pin "+") (pinfunction "+_+") (pintype "passive"))
      (node (ref "C21") (pin "+") (pinfunction "+_+") (pintype "passive"))
      (node (ref "J1") (pin "1") (pinfunction "1_1") (pintype "passive"))
      (node (ref "J10") (pin "3") (pinfunction "3_3") (pintype "power_in"))
      (node (ref "J10") (pin "4") (pinfunction "4_4") (pintype "power_in"))
      (node (ref "J4") (pin "1") (pinfunction "1_1") (pintype "passive"))
      (node (ref "J5") (pin "1") (pinfunction "1_1") (pintype "power_in"))
      (node (ref "J5") (pin "2") (pinfunction "2_2") (pintype "power_in"))
      (node (ref "J6") (pin "1") (pinfunction "S_1") (pintype "passive"))
      (node (ref "J6") (pin "2") (pinfunction "S_2") (pintype "passive"))
      (node (ref "J6") (pin "3") (pinfunction "S_3") (pintype "passive"))
      (node (ref "J7") (pin "3") (pinfunction "3_3") (pintype "power_in"))
      (node (ref "J7") (pin "4") (pinfunction "4_4") (pintype "power_in"))
      (node (ref "J8") (pin "3") (pinfunction "3_3") (pintype "passive"))
      (node (ref "J9") (pin "3") (pinfunction "3_3") (pintype "power_in"))
      (node (ref "J9") (pin "4") (pinfunction "4_4") (pintype "power_in"))
      (node (ref "JP4") (pin "1") (pinfunction "1_1") (pintype "passive"))
      (node (ref "JP6") (pin "1") (pinfunction "1_1") (pintype "passive"))
      (node (ref "P1") (pin "VMOT") (pinfunction "VMOT_VMOT") (pintype "power_in"))
      (node (ref "P2") (pin "VMOT") (pinfunction "VMOT_VMOT") (pintype "power_in"))
      (node (ref "P3") (pin "VMOT") (pinfunction "VMOT_VMOT") (pintype "power_in"))
      (node (ref "P4") (pin "VMOT") (pinfunction "VMOT_VMOT") (pintype "power_in"))
      (node (ref "P5") (pin "VMOT") (pinfunction "VMOT_VMOT") (pintype "power_in"))
      (node (ref "U1") (pin "4") (pinfunction "~{SHDN}_4") (pintype "input"))
      (node (ref "U1") (pin "5") (pinfunction "VIN_5") (pintype "power_in"))
    )
    (net (code "62") (name "GND") (class "Default")
      (node (ref "C1") (pin "2") (pinfunction "2_2") (pintype "passive"))
      (node (ref "C10") (pin "2") (pinfunction "2_2") (pintype "passive"))
      (node (ref "C11") (pin "2") (pinfunction "2_2") (pintype "passive"))
      (node (ref "C12") (pin "1") (pinfunction "1_1") (pintype "passive"))
      (node (ref "C13") (pin "1") (pinfunction "1_1") (pintype "passive"))
      (node (ref "C14") (pin "1") (pinfunction "1_1") (pintype "passive"))
      (node (ref "C15") (pin "1") (pinfunction "1_1") (pintype "passive"))
      (node (ref "C16") (pin "1") (pinfunction "1_1") (pintype "passive"))
      (node (ref "C17") (pin "-") (pinfunction "-_-") (pintype "passive"))
      (node (ref "C18") (pin "-") (pinfunction "-_-") (pintype "passive"))
      (node (ref "C19") (pin "-") (pinfunction "-_-") (pintype "passive"))
      (node (ref "C2") (pin "-") (pinfunction "-_-") (pintype "passive"))
      (node (ref "C20") (pin "-") (pinfunction "-_-") (pintype "passive"))
      (node (ref "C21") (pin "-") (pinfunction "-_-") (pintype "passive"))
      (node (ref "C3") (pin "2") (pinfunction "2_2") (pintype "passive"))
      (node (ref "C5") (pin "1") (pinfunction "1_1") (pintype "passive"))
      (node (ref "C6") (pin "1") (pinfunction "1_1") (pintype "passive"))
      (node (ref "C7") (pin "1") (pinfunction "1_1") (pintype "passive"))
      (node (ref "C8") (pin "2") (pinfunction "2_2") (pintype "passive"))
      (node (ref "C9") (pin "1") (pinfunction "1_1") (pintype "passive"))
      (node (ref "D1") (pin "A") (pinfunction "A_A") (pintype "passive"))
      (node (ref "D2") (pin "A") (pinfunction "A_A") (pintype "passive"))
      (node (ref "J1") (pin "2") (pinfunction "2_2") (pintype "passive"))
      (node (ref "J11") (pin "2") (pinfunction "2_2") (pintype "passive"))
      (node (ref "J12") (pin "2") (pinfunction "2_2") (pintype "passive"))
      (node (ref "J13") (pin "2") (pinfunction "2_2") (pintype "passive"))
      (node (ref "J2") (pin "6") (pinfunction "GND_6") (pintype "power_in"))
      (node (ref "J2") (pin "C1") (pinfunction "SHEILD_C1") (pintype "bidirectional"))
      (node (ref "J2") (pin "C2") (pinfunction "SHIELD_C2") (pintype "bidirectional"))
      (node (ref "J2") (pin "C3") (pinfunction "SHIELD_C3") (pintype "bidirectional"))
      (node (ref "J2") (pin "C4") (pinfunction "SHIELD_C4") (pintype "bidirectional"))
      (node (ref "J2") (pin "CD1") (pinfunction "CD1_CD1") (pintype "bidirectional"))
      (node (ref "J3") (pin "GND") (pinfunction "GND_GND") (pintype "bidirectional"))
      (node (ref "J3") (pin "GND1") (pinfunction "GND_GND1") (pintype "bidirectional"))
      (node (ref "J3") (pin "GND2") (pinfunction "GND_GND2") (pintype "bidirectional"))
      (node (ref "J3") (pin "GND3") (pinfunction "GND_GND3") (pintype "bidirectional"))
      (node (ref "J3") (pin "GND4") (pinfunction "GND_GND4") (pintype "bidirectional"))
      (node (ref "J3") (pin "GND5") (pinfunction "GND_GND5") (pintype "bidirectional"))
      (node (ref "J3") (pin "GND6") (pinfunction "GND_GND6") (pintype "bidirectional"))
      (node (ref "J3") (pin "GND7") (pinfunction "GND_GND7") (pintype "bidirectional"))
      (node (ref "J3") (pin "GND8") (pinfunction "GND_GND8") (pintype "bidirectional"))
      (node (ref "J5") (pin "3") (pinfunction "3_3") (pintype "power_in"))
      (node (ref "J5") (pin "4") (pinfunction "4_4") (pintype "power_in"))
      (node (ref "J6") (pin "4") (pinfunction "S_4") (pintype "passive"))
      (node (ref "J6") (pin "5") (pinfunction "S_5") (pintype "passive"))
      (node (ref "J6") (pin "6") (pinfunction "S_6") (pintype "passive"))
      (node (ref "J8") (pin "1") (pinfunction "1_1") (pintype "passive"))
      (node (ref "JP10") (pin "3") (pinfunction "3_3") (pintype "passive"))
      (node (ref "JP3") (pin "2") (pinfunction "2_2") (pintype "passive"))
      (node (ref "JP5") (pin "1") (pinfunction "1_1") (pintype "passive"))
      (node (ref "JP7") (pin "3") (pinfunction "3_3") (pintype "passive"))
      (node (ref "JP8") (pin "3") (pinfunction "3_3") (pintype "passive"))
      (node (ref "JP9") (pin "3") (pinfunction "3_3") (pintype "passive"))
      (node (ref "LED1") (pin "C") (pinfunction "C_C") (pintype "passive"))
      (node (ref "P1") (pin "GNDMOT") (pinfunction "GNDMOT_GNDMOT") (pintype "power_in"))
      (node (ref "P1") (pin "GNDVDD") (pinfunction "GNDVDD_GNDVDD") (pintype "power_in"))
      (node (ref "P2") (pin "GNDMOT") (pinfunction "GNDMOT_GNDMOT") (pintype "power_in"))
      (node (ref "P2") (pin "GNDVDD") (pinfunction "GNDVDD_GNDVDD") (pintype "power_in"))
      (node (ref "P3") (pin "GNDMOT") (pinfunction "GNDMOT_GNDMOT") (pintype "power_in"))
      (node (ref "P3") (pin "GNDVDD") (pinfunction "GNDVDD_GNDVDD") (pintype "power_in"))
      (node (ref "P4") (pin "GNDMOT") (pinfunction "GNDMOT_GNDMOT") (pintype "power_in"))
      (node (ref "P4") (pin "GNDVDD") (pinfunction "GNDVDD_GNDVDD") (pintype "power_in"))
      (node (ref "P5") (pin "GNDMOT") (pinfunction "GNDMOT_GNDMOT") (pintype "power_in"))
      (node (ref "P5") (pin "GNDVDD") (pinfunction "GNDVDD_GNDVDD") (pintype "power_in"))
      (node (ref "Q1") (pin "2") (pinfunction "S_2") (pintype "passive"))
      (node (ref "Q2") (pin "1") (pinfunction "S1_1") (pintype "passive"))
      (node (ref "Q2") (pin "2") (pinfunction "S2_2") (pintype "passive"))
      (node (ref "Q2") (pin "3") (pinfunction "S3_3") (pintype "passive"))
      (node (ref "Q3") (pin "1") (pinfunction "S1_1") (pintype "passive"))
      (node (ref "Q3") (pin "2") (pinfunction "S2_2") (pintype "passive"))
      (node (ref "Q3") (pin "3") (pinfunction "S3_3") (pintype "passive"))
      (node (ref "Q4") (pin "1") (pinfunction "S1_1") (pintype "passive"))
      (node (ref "Q4") (pin "2") (pinfunction "S2_2") (pintype "passive"))
      (node (ref "Q4") (pin "3") (pinfunction "S3_3") (pintype "passive"))
      (node (ref "Q5") (pin "2") (pinfunction "E_2") (pintype "passive"))
      (node (ref "R10") (pin "2") (pinfunction "2_2") (pintype "passive"))
      (node (ref "R14") (pin "2") (pinfunction "2_2") (pintype "passive"))
      (node (ref "R2") (pin "2") (pinfunction "2_2") (pintype "passive"))
      (node (ref "R5") (pin "2") (pinfunction "2_2") (pintype "passive"))
      (node (ref "R8") (pin "2") (pinfunction "2_2") (pintype "passive"))
      (node (ref "S1") (pin "1") (pinfunction "1_1") (pintype "passive"))
      (node (ref "S1") (pin "2") (pinfunction "2_2") (pintype "passive"))
      (node (ref "SCREW1") (pin "GND") (pinfunction "P$1_GND") (pintype "bidirectional"))
      (node (ref "SCREW2") (pin "GND") (pinfunction "P$1_GND") (pintype "bidirectional"))
      (node (ref "SCREW3") (pin "GND") (pinfunction "P$1_GND") (pintype "bidirectional"))
      (node (ref "SCREW4") (pin "GND") (pinfunction "P$1_GND") (pintype "bidirectional"))
      (node (ref "U1") (pin "2") (pinfunction "GND_2") (pintype "power_in"))
      (node (ref "U2") (pin "2") (pinfunction "GND_2") (pintype "power_in"))
      (node (ref "U3") (pin "3") (pinfunction "GND_3") (pintype "power_in"))
      (node (ref "U4") (pin "7") (pinfunction "GND_7") (pintype "power_in"))
      (node (ref "U5") (pin "22") (pinfunction "GND_22") (pintype "power_in"))
      (node (ref "U5") (pin "53") (pinfunction "GND_53") (pintype "power_in"))
      (node (ref "U5") (pin "6") (pinfunction "UGND_6") (pintype "power_in"))
      (node (ref "U5") (pin "63") (pinfunction "AGND_63") (pintype "power_in"))
    )
    (net (code "63") (name "Net-(F1-PadP$2)") (class "Default")
      (node (ref "F1") (pin "P$2") (pinfunction "P$2_P$2") (pintype "passive"))
      (node (ref "J4") (pin "2") (pinfunction "2_2") (pintype "passive"))
    )
    (net (code "64") (name "Net-(JP6-Pad2)") (class "Default")
      (node (ref "JP6") (pin "2") (pinfunction "2_2") (pintype "passive"))
      (node (ref "JP7") (pin "2") (pinfunction "2_2") (pintype "passive"))
    )
    (net (code "65") (name "Net-(JP10-Pad2)") (class "Default")
      (node (ref "JP10") (pin "2") (pinfunction "2_2") (pintype "passive"))
      (node (ref "JP4") (pin "2") (pinfunction "2_2") (pintype "passive"))
      (node (ref "JP8") (pin "2") (pinfunction "2_2") (pintype "passive"))
      (node (ref "JP9") (pin "2") (pinfunction "2_2") (pintype "passive"))
    )
    (net (code "66") (name "Net-(LED1-PadA)") (class "Default")
      (node (ref "LED1") (pin "A") (pinfunction "A_A") (pintype "passive"))
      (node (ref "R1") (pin "1") (pinfunction "1_1") (pintype "passive"))
    )
    (net (code "67") (name "Net-(P1-MOT-1A)") (class "Default")
      (node (ref "JP11") (pin "2") (pinfunction "2_2") (pintype "passive"))
      (node (ref "P1") (pin "1A") (pinfunction "MOT-1A_1A") (pintype "power_in"))
    )
    (net (code "68") (name "Net-(P1-MOT-1B)") (class "Default")
      (node (ref "JP11") (pin "1") (pinfunction "1_1") (pintype "passive"))
      (node (ref "P1") (pin "1B") (pinfunction "MOT-1B_1B") (pintype "power_in"))
    )
    (net (code "69") (name "Net-(P1-MOT-2A)") (class "Default")
      (node (ref "JP11") (pin "3") (pinfunction "3_3") (pintype "passive"))
      (node (ref "P1") (pin "2A") (pinfunction "MOT-2A_2A") (pintype "power_in"))
    )
    (net (code "70") (name "Net-(P1-MOT-2B)") (class "Default")
      (node (ref "JP11") (pin "4") (pinfunction "4_4") (pintype "passive"))
      (node (ref "P1") (pin "2B") (pinfunction "MOT-2B_2B") (pintype "power_in"))
    )
    (net (code "71") (name "Net-(P1-PadMS1)") (class "Default")
      (node (ref "P1") (pin "MS1") (pinfunction "MS1_MS1") (pintype "input"))
      (node (ref "SJ12") (pin "1") (pinfunction "1_1") (pintype "passive"))
    )
    (net (code "72") (name "Net-(P1-PadMS2)") (class "Default")
      (node (ref "P1") (pin "MS2") (pinfunction "MS2_MS2") (pintype "input"))
      (node (ref "SJ7") (pin "1") (pinfunction "1_1") (pintype "passive"))
    )
    (net (code "73") (name "Net-(P1-PadMS3)") (class "Default")
      (node (ref "P1") (pin "MS3") (pinfunction "MS3_MS3") (pintype "input"))
      (node (ref "SJ2") (pin "1") (pinfunction "1_1") (pintype "passive"))
    )
    (net (code "74") (name "Net-(P1-~{RESET})") (class "Default")
      (node (ref "P1") (pin "!RST") (pinfunction "~{RESET}_!RST") (pintype "input"))
      (node (ref "P1") (pin "!SLP") (pinfunction "~{SLEEP}_!SLP") (pintype "input"))
    )
    (net (code "75") (name "Net-(P2-MOT-1A)") (class "Default")
      (node (ref "JP12") (pin "2") (pinfunction "2_2") (pintype "passive"))
      (node (ref "P2") (pin "1A") (pinfunction "MOT-1A_1A") (pintype "power_in"))
    )
    (net (code "76") (name "Net-(P2-MOT-1B)") (class "Default")
      (node (ref "JP12") (pin "1") (pinfunction "1_1") (pintype "passive"))
      (node (ref "P2") (pin "1B") (pinfunction "MOT-1B_1B") (pintype "power_in"))
    )
    (net (code "77") (name "Net-(P2-MOT-2A)") (class "Default")
      (node (ref "JP12") (pin "3") (pinfunction "3_3") (pintype "passive"))
      (node (ref "P2") (pin "2A") (pinfunction "MOT-2A_2A") (pintype "power_in"))
    )
    (net (code "78") (name "Net-(P2-MOT-2B)") (class "Default")
      (node (ref "JP12") (pin "4") (pinfunction "4_4") (pintype "passive"))
      (node (ref "P2") (pin "2B") (pinfunction "MOT-2B_2B") (pintype "power_in"))
    )
    (net (code "79") (name "Net-(P2-PadMS1)") (class "Default")
      (node (ref "P2") (pin "MS1") (pinfunction "MS1_MS1") (pintype "input"))
      (node (ref "SJ13") (pin "1") (pinfunction "1_1") (pintype "passive"))
    )
    (net (code "80") (name "Net-(P2-PadMS2)") (class "Default")
      (node (ref "P2") (pin "MS2") (pinfunction "MS2_MS2") (pintype "input"))
      (node (ref "SJ8") (pin "1") (pinfunction "1_1") (pintype "passive"))
    )
    (net (code "81") (name "Net-(P2-PadMS3)") (class "Default")
      (node (ref "P2") (pin "MS3") (pinfunction "MS3_MS3") (pintype "input"))
      (node (ref "SJ3") (pin "1") (pinfunction "1_1") (pintype "passive"))
    )
    (net (code "82") (name "Net-(P2-~{RESET})") (class "Default")
      (node (ref "P2") (pin "!RST") (pinfunction "~{RESET}_!RST") (pintype "input"))
      (node (ref "P2") (pin "!SLP") (pinfunction "~{SLEEP}_!SLP") (pintype "input"))
    )
    (net (code "83") (name "Net-(P3-MOT-1A)") (class "Default")
      (node (ref "JP15") (pin "2") (pinfunction "2_2") (pintype "passive"))
      (node (ref "P3") (pin "1A") (pinfunction "MOT-1A_1A") (pintype "power_in"))
    )
    (net (code "84") (name "Net-(P3-MOT-1B)") (class "Default")
      (node (ref "JP15") (pin "1") (pinfunction "1_1") (pintype "passive"))
      (node (ref "P3") (pin "1B") (pinfunction "MOT-1B_1B") (pintype "power_in"))
    )
    (net (code "85") (name "Net-(P3-MOT-2A)") (class "Default")
      (node (ref "JP15") (pin "3") (pinfunction "3_3") (pintype "passive"))
      (node (ref "P3") (pin "2A") (pinfunction "MOT-2A_2A") (pintype "power_in"))
    )
    (net (code "86") (name "Net-(P3-MOT-2B)") (class "Default")
      (node (ref "JP15") (pin "4") (pinfunction "4_4") (pintype "passive"))
      (node (ref "P3") (pin "2B") (pinfunction "MOT-2B_2B") (pintype "power_in"))
    )
    (net (code "87") (name "Net-(P3-PadMS1)") (class "Default")
      (node (ref "P3") (pin "MS1") (pinfunction "MS1_MS1") (pintype "input"))
      (node (ref "SJ14") (pin "1") (pinfunction "1_1") (pintype "passive"))
    )
    (net (code "88") (name "Net-(P3-PadMS2)") (class "Default")
      (node (ref "P3") (pin "MS2") (pinfunction "MS2_MS2") (pintype "input"))
      (node (ref "SJ9") (pin "1") (pinfunction "1_1") (pintype "passive"))
    )
    (net (code "89") (name "Net-(P3-PadMS3)") (class "Default")
      (node (ref "P3") (pin "MS3") (pinfunction "MS3_MS3") (pintype "input"))
      (node (ref "SJ4") (pin "1") (pinfunction "1_1") (pintype "passive"))
    )
    (net (code "90") (name "Net-(P3-~{RESET})") (class "Default")
      (node (ref "P3") (pin "!RST") (pinfunction "~{RESET}_!RST") (pintype "input"))
      (node (ref "P3") (pin "!SLP") (pinfunction "~{SLEEP}_!SLP") (pintype "input"))
    )
    (net (code "91") (name "Net-(P4-MOT-1A)") (class "Default")
      (node (ref "JP13") (pin "2") (pinfunction "2_2") (pintype "passive"))
      (node (ref "P4") (pin "1A") (pinfunction "MOT-1A_1A") (pintype "power_in"))
    )
    (net (code "92") (name "Net-(P4-MOT-1B)") (class "Default")
      (node (ref "JP13") (pin "1") (pinfunction "1_1") (pintype "passive"))
      (node (ref "P4") (pin "1B") (pinfunction "MOT-1B_1B") (pintype "power_in"))
    )
    (net (code "93") (name "Net-(P4-MOT-2A)") (class "Default")
      (node (ref "JP13") (pin "3") (pinfunction "3_3") (pintype "passive"))
      (node (ref "P4") (pin "2A") (pinfunction "MOT-2A_2A") (pintype "power_in"))
    )
    (net (code "94") (name "Net-(P4-MOT-2B)") (class "Default")
      (node (ref "JP13") (pin "4") (pinfunction "4_4") (pintype "passive"))
      (node (ref "P4") (pin "2B") (pinfunction "MOT-2B_2B") (pintype "power_in"))
    )
    (net (code "95") (name "Net-(P4-PadMS1)") (class "Default")
      (node (ref "P4") (pin "MS1") (pinfunction "MS1_MS1") (pintype "input"))
      (node (ref "SJ15") (pin "1") (pinfunction "1_1") (pintype "passive"))
    )
    (net (code "96") (name "Net-(P4-PadMS2)") (class "Default")
      (node (ref "P4") (pin "MS2") (pinfunction "MS2_MS2") (pintype "input"))
      (node (ref "SJ10") (pin "1") (pinfunction "1_1") (pintype "passive"))
    )
    (net (code "97") (name "Net-(P4-PadMS3)") (class "Default")
      (node (ref "P4") (pin "MS3") (pinfunction "MS3_MS3") (pintype "input"))
      (node (ref "SJ5") (pin "1") (pinfunction "1_1") (pintype "passive"))
    )
    (net (code "98") (name "Net-(P4-~{RESET})") (class "Default")
      (node (ref "P4") (pin "!RST") (pinfunction "~{RESET}_!RST") (pintype "input"))
      (node (ref "P4") (pin "!SLP") (pinfunction "~{SLEEP}_!SLP") (pintype "input"))
    )
    (net (code "99") (name "Net-(P5-MOT-1A)") (class "Default")
      (node (ref "JP14") (pin "2") (pinfunction "2_2") (pintype "passive"))
      (node (ref "P5") (pin "1A") (pinfunction "MOT-1A_1A") (pintype "power_in"))
    )
    (net (code "100") (name "Net-(P5-MOT-1B)") (class "Default")
      (node (ref "JP14") (pin "1") (pinfunction "1_1") (pintype "passive"))
      (node (ref "P5") (pin "1B") (pinfunction "MOT-1B_1B") (pintype "power_in"))
    )
    (net (code "101") (name "Net-(P5-MOT-2A)") (class "Default")
      (node (ref "JP14") (pin "3") (pinfunction "3_3") (pintype "passive"))
      (node (ref "P5") (pin "2A") (pinfunction "MOT-2A_2A") (pintype "power_in"))
    )
    (net (code "102") (name "Net-(P5-MOT-2B)") (class "Default")
      (node (ref "JP14") (pin "4") (pinfunction "4_4") (pintype "passive"))
      (node (ref "P5") (pin "2B") (pinfunction "MOT-2B_2B") (pintype "power_in"))
    )
    (net (code "103") (name "Net-(P5-PadMS1)") (class "Default")
      (node (ref "P5") (pin "MS1") (pinfunction "MS1_MS1") (pintype "input"))
      (node (ref "SJ16") (pin "1") (pinfunction "1_1") (pintype "passive"))
    )
    (net (code "104") (name "Net-(P5-PadMS2)") (class "Default")
      (node (ref "P5") (pin "MS2") (pinfunction "MS2_MS2") (pintype "input"))
      (node (ref "SJ11") (pin "1") (pinfunction "1_1") (pintype "passive"))
    )
    (net (code "105") (name "Net-(P5-PadMS3)") (class "Default")
      (node (ref "P5") (pin "MS3") (pinfunction "MS3_MS3") (pintype "input"))
      (node (ref "SJ6") (pin "1") (pinfunction "1_1") (pintype "passive"))
    )
    (net (code "106") (name "Net-(P5-~{RESET})") (class "Default")
      (node (ref "P5") (pin "!RST") (pinfunction "~{RESET}_!RST") (pintype "input"))
      (node (ref "P5") (pin "!SLP") (pinfunction "~{SLEEP}_!SLP") (pintype "input"))
    )
    (net (code "107") (name "Net-(Q1-D)") (class "Default")
      (node (ref "D2") (pin "C") (pinfunction "C_C") (pintype "passive"))
      (node (ref "F1") (pin "P$1") (pinfunction "P$1_P$1") (pintype "passive"))
      (node (ref "Q1") (pin "3") (pinfunction "D_3") (pintype "passive"))
    )
    (net (code "108") (name "Net-(Q1-G)") (class "Default")
      (node (ref "Q1") (pin "1") (pinfunction "G_1") (pintype "passive"))
      (node (ref "R3") (pin "2") (pinfunction "2_2") (pintype "passive"))
    )
    (net (code "109") (name "Net-(Q2-D)") (class "Default")
      (node (ref "J7") (pin "1") (pinfunction "1_1") (pintype "power_in"))
      (node (ref "J7") (pin "2") (pinfunction "2_2") (pintype "power_in"))
      (node (ref "Q2") (pin "5-8") (pinfunction "D_5-8") (pintype "passive"))
    )
    (net (code "110") (name "Net-(Q2-G)") (class "Default")
      (node (ref "Q2") (pin "4") (pinfunction "G_4") (pintype "passive"))
      (node (ref "R9") (pin "2") (pinfunction "2_2") (pintype "passive"))
    )
    (net (code "111") (name "Net-(Q3-D)") (class "Default")
      (node (ref "J9") (pin "1") (pinfunction "1_1") (pintype "power_in"))
      (node (ref "J9") (pin "2") (pinfunction "2_2") (pintype "power_in"))
      (node (ref "Q3") (pin "5-8") (pinfunction "D_5-8") (pintype "passive"))
    )
    (net (code "112") (name "Net-(Q3-G)") (class "Default")
      (node (ref "Q3") (pin "4") (pinfunction "G_4") (pintype "passive"))
      (node (ref "R11") (pin "2") (pinfunction "2_2") (pintype "passive"))
    )
    (net (code "113") (name "Net-(Q4-D)") (class "Default")
      (node (ref "J10") (pin "1") (pinfunction "1_1") (pintype "power_in"))
      (node (ref "J10") (pin "2") (pinfunction "2_2") (pintype "power_in"))
      (node (ref "Q4") (pin "5-8") (pinfunction "D_5-8") (pintype "passive"))
    )
    (net (code "114") (name "Net-(Q4-G)") (class "Default")
      (node (ref "Q4") (pin "4") (pinfunction "G_4") (pintype "passive"))
      (node (ref "R15") (pin "2") (pinfunction "2_2") (pintype "passive"))
    )
    (net (code "115") (name "Net-(Q5-B)") (class "Default")
      (node (ref "JP7") (pin "1") (pinfunction "1_1") (pintype "passive"))
      (node (ref "Q5") (pin "1") (pinfunction "B_1") (pintype "passive"))
    )
    (net (code "116") (name "Net-(U1-CB)") (class "Default")
      (node (ref "C4") (pin "2") (pinfunction "2_2") (pintype "passive"))
      (node (ref "U1") (pin "1") (pinfunction "CB_1") (pintype "passive"))
    )
    (net (code "117") (name "Net-(U1-FB)") (class "Default")
      (node (ref "R4") (pin "2") (pinfunction "2_2") (pintype "passive"))
      (node (ref "R5") (pin "1") (pinfunction "1_1") (pintype "passive"))
      (node (ref "U1") (pin "3") (pinfunction "FB_3") (pintype "passive"))
    )
    (net (code "118") (name "Net-(U1-SW)") (class "Default")
      (node (ref "C4") (pin "1") (pinfunction "1_1") (pintype "passive"))
      (node (ref "D1") (pin "C") (pinfunction "C_C") (pintype "passive"))
      (node (ref "L1") (pin "1") (pinfunction "1_1") (pintype "passive"))
      (node (ref "U1") (pin "6") (pinfunction "SW_6") (pintype "passive"))
    )
    (net (code "119") (name "Net-(U5-D+)") (class "Default")
      (node (ref "R7") (pin "2") (pinfunction "2_2") (pintype "passive"))
      (node (ref "U5") (pin "5") (pinfunction "D+_5") (pintype "bidirectional"))
    )
    (net (code "120") (name "Net-(U5-D-)") (class "Default")
      (node (ref "R6") (pin "2") (pinfunction "2_2") (pintype "passive"))
      (node (ref "U5") (pin "4") (pinfunction "D-_4") (pintype "bidirectional"))
    )
    (net (code "121") (name "Net-(U5-UCAP)") (class "Default")
      (node (ref "C9") (pin "2") (pinfunction "2_2") (pintype "passive"))
      (node (ref "U5") (pin "7") (pinfunction "UCAP_7") (pintype "power_in"))
    )
    (net (code "122") (name "unconnected-(J2-DAT1-Pad8)") (class "Default")
      (node (ref "J2") (pin "8") (pinfunction "DAT1_8") (pintype "bidirectional"))
    )
    (net (code "123") (name "unconnected-(J2-DAT2-Pad1)") (class "Default")
      (node (ref "J2") (pin "1") (pinfunction "DAT2_1") (pintype "bidirectional"))
    )
    (net (code "124") (name "unconnected-(U2-IO3-Pad4)") (class "Default")
      (node (ref "U2") (pin "4") (pinfunction "IO3_4") (pintype "bidirectional"))
    )
    (net (code "125") (name "unconnected-(U2-IO4-Pad6)") (class "Default")
      (node (ref "U2") (pin "6") (pinfunction "IO4_6") (pintype "bidirectional"))
    )
  )
)
